# BMS_watchdog.net
KiCad netlist of a schematic drawn in EAGLE
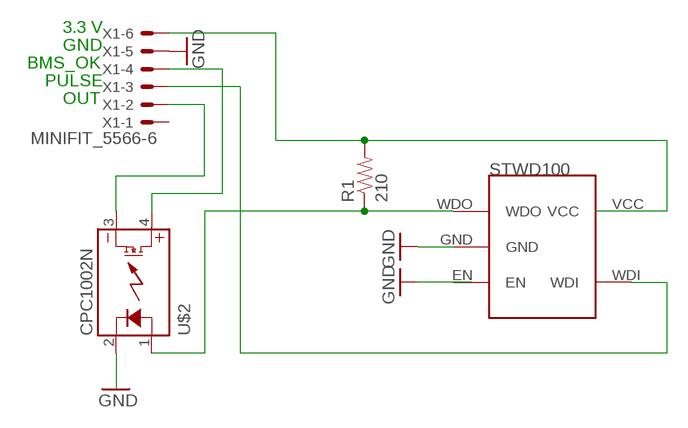
[diagram p0: schematic, sheet 1]

(export (version "E")
  (design (tool "Eeschema 10.0.6"))
  (components
    (comp (ref "R1")
      (value "210")
      (footprint "eagle-import:0805")
      (libsource (lib "eagle-import") (part "RESISTOR0805-RES"))
    )
    (comp (ref "U$1")
      (value "STWD100")
      (footprint "eagle-import:SOT23-5")
      (libsource (lib "eagle-import") (part "STWD100"))
    )
    (comp (ref "U$2")
      (value "CPC1002N")
      (footprint "eagle-import:SOP04")
      (libsource (lib "eagle-import") (part "CPC1002N"))
    )
    (comp (ref "X1")
      (value "MINIFIT_5566-6")
      (footprint "eagle-import:MINIFIT_5566-6")
      (fields (field (name "MPN") "95566-61002"))
      (libsource (lib "eagle-import") (part "MINIFIT_5566-6"))
    )
  )
  (nets
    (net (code "1") (name "GND") (class "Default")
      (node (ref "U$1") (pin "GND") (pinfunction "GND_GND") (pintype "bidirectional"))
      (node (ref "X1") (pin "5") (pinfunction "S_5") (pintype "passive"))
    )
    (net (code "2") (name "Net-(U$2-CONTROL+)") (class "Default")
      (node (ref "R1") (pin "1") (pinfunction "1_1") (pintype "passive"))
      (node (ref "U$1") (pin "WDO") (pinfunction "WDO_WDO") (pintype "bidirectional"))
      (node (ref "U$2") (pin "1") (pinfunction "CONTROL+_1") (pintype "passive"))
    )
    (net (code "3") (name "Net-(U$2-DC+)") (class "Default")
      (node (ref "U$2") (pin "4") (pinfunction "DC+_4") (pintype "passive"))
      (node (ref "X1") (pin "4") (pinfunction "S_4") (pintype "passive"))
    )
    (net (code "4") (name "Net-(U$2-DC-)") (class "Default")
      (node (ref "U$2") (pin "3") (pinfunction "DC-_3") (pintype "passive"))
      (node (ref "X1") (pin "2") (pinfunction "S_2") (pintype "passive"))
    )
    (net (code "5") (name "Net-(X1C-S)") (class "Default")
      (node (ref "U$1") (pin "WDI") (pinfunction "WDI_WDI") (pintype "bidirectional"))
      (node (ref "X1") (pin "3") (pinfunction "S_3") (pintype "passive"))
    )
    (net (code "6") (name "Net-(X1F-S)") (class "Default")
      (node (ref "R1") (pin "2") (pinfunction "2_2") (pintype "passive"))
      (node (ref "X1") (pin "6") (pinfunction "S_6") (pintype "passive"))
    )
    (net (code "7") (name "unconnected-(U$1-PadEN)") (class "Default")
      (node (ref "U$1") (pin "EN") (pinfunction "EN_EN") (pintype "bidirectional"))
    )
    (net (code "8") (name "unconnected-(U$1-PadVCC)") (class "Default")
      (node (ref "U$1") (pin "VCC") (pinfunction "VCC_VCC") (pintype "bidirectional"))
    )
    (net (code "9") (name "unconnected-(U$2-CONTROL--Pad2)") (class "Default")
      (node (ref "U$2") (pin "2") (pinfunction "CONTROL-_2") (pintype "passive"))
    )
    (net (code "10") (name "unconnected-(X1A-S-Pad1)") (class "Default")
      (node (ref "X1") (pin "1") (pinfunction "S_1") (pintype "passive"))
    )
  )
)
